# DP10.net
KiCad netlist of a schematic drawn in Altium Designer
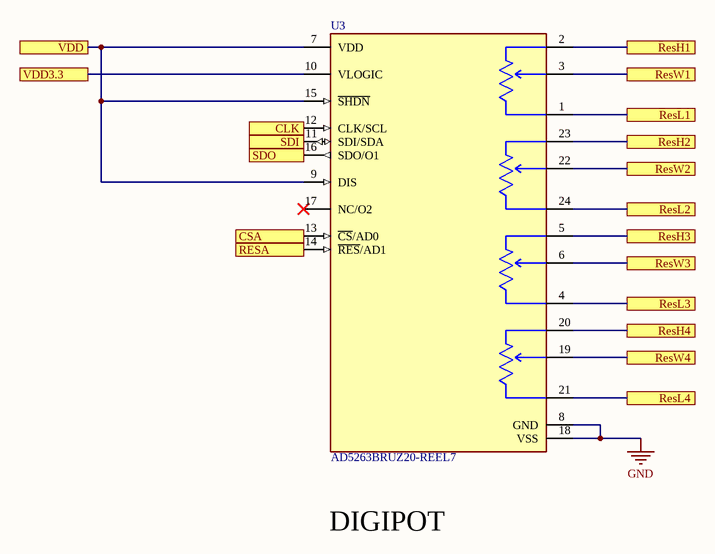
[diagram p0: DP10.SchDoc]

(export (version "E")
  (design (tool "Eeschema 10.0.6"))
  (components
    (comp (ref "U3")
      (value "AD5263BRUZ20-REEL7")
      (footprint "FP-RU-24-IPC_A")
      (description "IC DGT POT 50KOHM 256TAP 24TSSOP")
      (fields (field (name "TOLERANCE") "30%"))
      (libsource (lib "Altium Content Vault") (part "8f750aaeae090b847826f69f71e761e"))
    )
  )
  (nets
    (net (code "1") (name "/CLK") (class "Default")
      (node (ref "U3") (pin "12") (pinfunction "CLK/SCL_12") (pintype "input"))
    )
    (net (code "2") (name "/CSA") (class "Default")
      (node (ref "U3") (pin "13") (pinfunction "~{CS}/AD0_13") (pintype "input"))
    )
    (net (code "3") (name "/RESA") (class "Default")
      (node (ref "U3") (pin "14") (pinfunction "~{RES}/AD1_14") (pintype "input"))
    )
    (net (code "4") (name "/ResH1") (class "Default")
      (node (ref "U3") (pin "2") (pinfunction "A1_2") (pintype "passive"))
    )
    (net (code "5") (name "/ResH2") (class "Default")
      (node (ref "U3") (pin "23") (pinfunction "A2_23") (pintype "passive"))
    )
    (net (code "6") (name "/ResH3") (class "Default")
      (node (ref "U3") (pin "5") (pinfunction "A3_5") (pintype "passive"))
    )
    (net (code "7") (name "/ResH4") (class "Default")
      (node (ref "U3") (pin "20") (pinfunction "A4_20") (pintype "passive"))
    )
    (net (code "8") (name "/ResL1") (class "Default")
      (node (ref "U3") (pin "1") (pinfunction "B1_1") (pintype "passive"))
    )
    (net (code "9") (name "/ResL2") (class "Default")
      (node (ref "U3") (pin "24") (pinfunction "B2_24") (pintype "passive"))
    )
    (net (code "10") (name "/ResL3") (class "Default")
      (node (ref "U3") (pin "4") (pinfunction "B3_4") (pintype "passive"))
    )
    (net (code "11") (name "/ResL4") (class "Default")
      (node (ref "U3") (pin "21") (pinfunction "B4_21") (pintype "passive"))
    )
    (net (code "12") (name "/ResW1") (class "Default")
      (node (ref "U3") (pin "3") (pinfunction "W1_3") (pintype "passive"))
    )
    (net (code "13") (name "/ResW2") (class "Default")
      (node (ref "U3") (pin "22") (pinfunction "W2_22") (pintype "passive"))
    )
    (net (code "14") (name "/ResW3") (class "Default")
      (node (ref "U3") (pin "6") (pinfunction "W3_6") (pintype "passive"))
    )
    (net (code "15") (name "/ResW4") (class "Default")
      (node (ref "U3") (pin "19") (pinfunction "W4_19") (pintype "passive"))
    )
    (net (code "16") (name "/SDI") (class "Default")
      (node (ref "U3") (pin "11") (pinfunction "SDI/SDA_11") (pintype "bidirectional"))
    )
    (net (code "17") (name "/SDO") (class "Default")
      (node (ref "U3") (pin "16") (pinfunction "SDO/O1_16") (pintype "output"))
    )
    (net (code "18") (name "/VDD") (class "Default")
      (node (ref "U3") (pin "15") (pinfunction "~{SHDN}_15") (pintype "input"))
      (node (ref "U3") (pin "7") (pinfunction "VDD_7") (pintype "power_in"))
      (node (ref "U3") (pin "9") (pinfunction "DIS_9") (pintype "input"))
    )
    (net (code "19") (name "/VDD3.3") (class "Default")
      (node (ref "U3") (pin "10") (pinfunction "VLOGIC_10") (pintype "power_in"))
    )
    (net (code "20") (name "GND") (class "Default")
      (node (ref "U3") (pin "18") (pinfunction "VSS_18") (pintype "power_in"))
      (node (ref "U3") (pin "8") (pinfunction "GND_8") (pintype "power_in"))
    )
    (net (code "21") (name "unconnected-(U3-NC{slash}O2-Pad17)") (class "Default")
      (node (ref "U3") (pin "17") (pinfunction "NC/O2_17") (pintype "passive+no_connect"))
    )
  )
)
